# needles_2_5.net
KiCad netlist of a schematic drawn in EAGLE
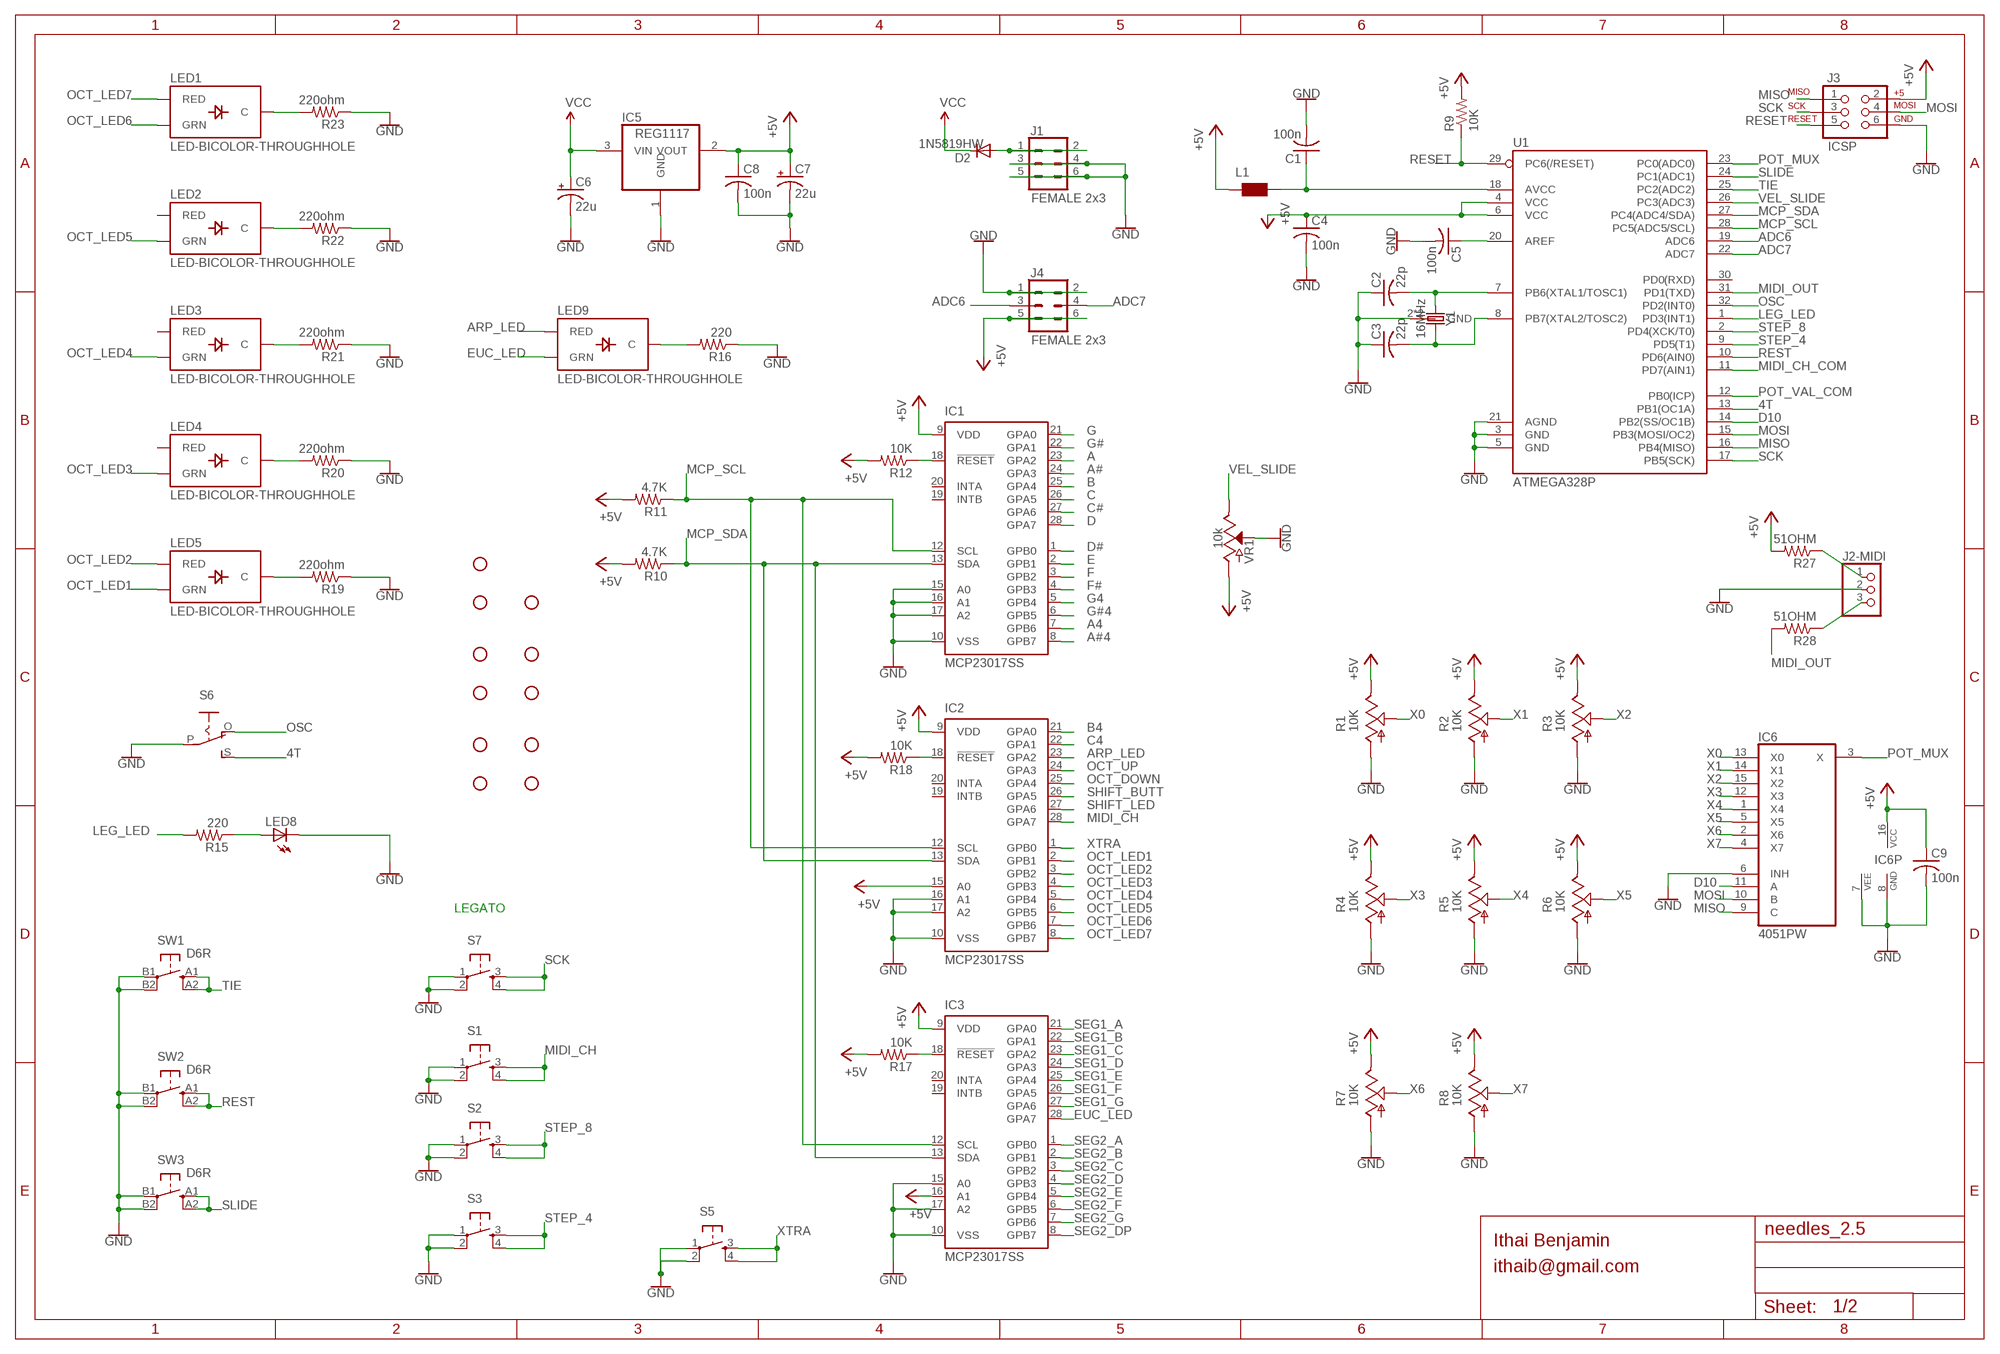
[diagram p0: schematic, sheet 1]
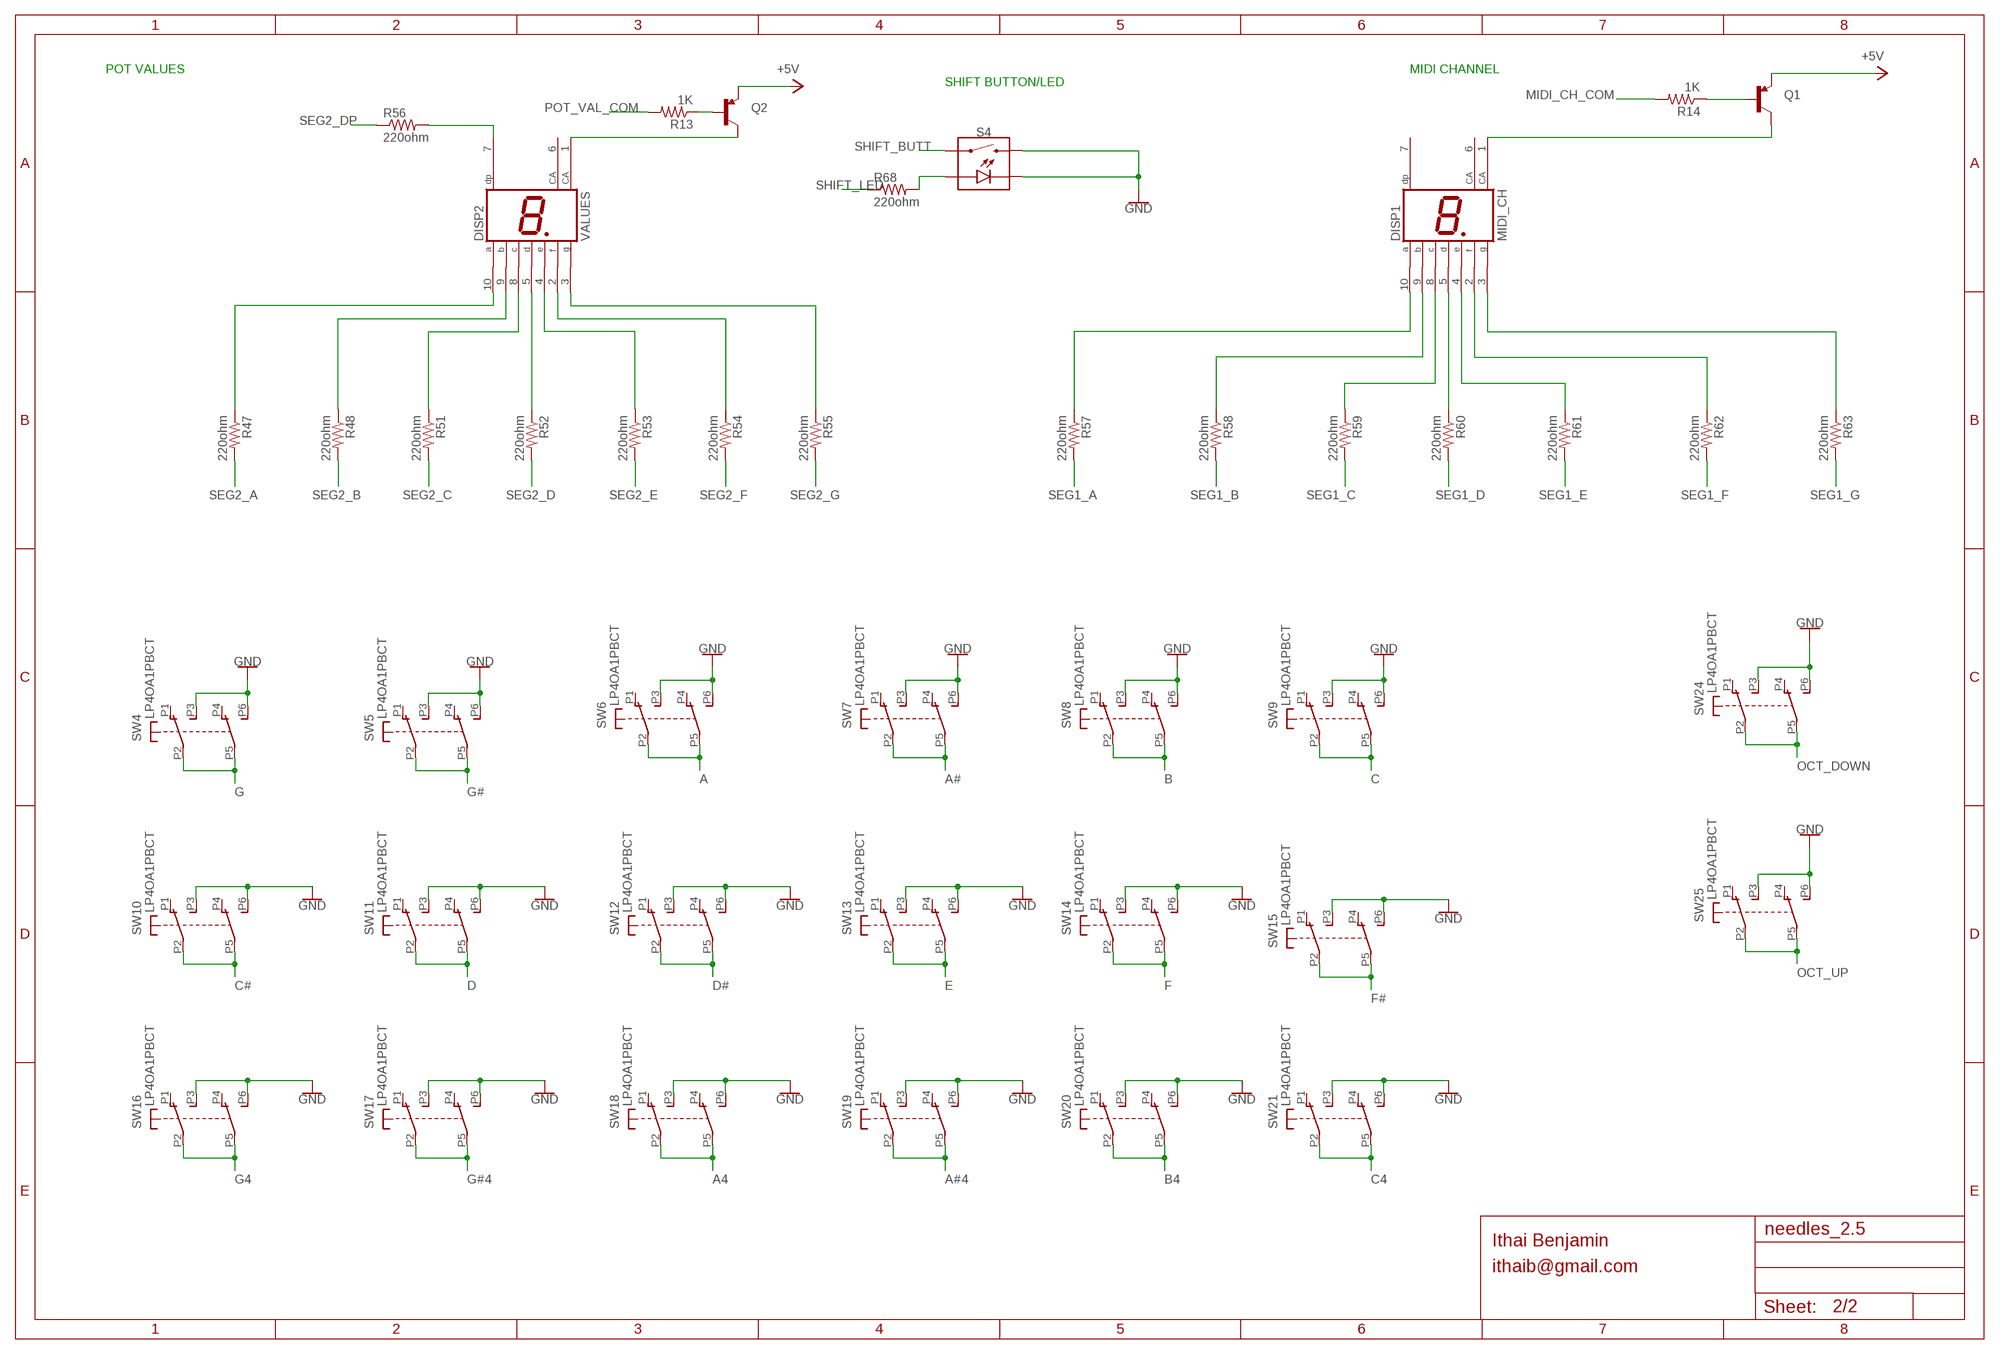
[diagram p1: schematic, sheet 2]

(export (version "E")
  (design (tool "Eeschema 10.0.6"))
  (components
    (comp (ref "DISP1")
      (value "MIDI_CH")
      (footprint "eagle-import:DISPLAY-HP_HDSP-E")
      (libsource (lib "eagle-import") (part "DISPLAY-HP_HD-F101"))
    )
    (comp (ref "DISP2")
      (value "VALUES")
      (footprint "eagle-import:DISPLAY-HP_HDSP-E")
      (libsource (lib "eagle-import") (part "DISPLAY-HP_HD-F101"))
    )
    (comp (ref "Q1")
      (value "TRANSISTOR_PNPSMD")
      (footprint "eagle-import:SOT23-3")
      (libsource (lib "eagle-import") (part "TRANSISTOR_PNPSMD"))
    )
    (comp (ref "Q2")
      (value "TRANSISTOR_PNPSMD")
      (footprint "eagle-import:SOT23-3")
      (libsource (lib "eagle-import") (part "TRANSISTOR_PNPSMD"))
    )
    (comp (ref "R13")
      (value "1K")
      (footprint "eagle-import:R0603")
      (libsource (lib "eagle-import") (part "R-US_R0603"))
    )
    (comp (ref "R14")
      (value "1K")
      (footprint "eagle-import:R0603")
      (libsource (lib "eagle-import") (part "R-US_R0603"))
    )
    (comp (ref "R47")
      (value "220ohm")
      (footprint "eagle-import:R0603")
      (libsource (lib "eagle-import") (part "R-US_R0603"))
    )
    (comp (ref "R48")
      (value "220ohm")
      (footprint "eagle-import:R0603")
      (libsource (lib "eagle-import") (part "R-US_R0603"))
    )
    (comp (ref "R51")
      (value "220ohm")
      (footprint "eagle-import:R0603")
      (libsource (lib "eagle-import") (part "R-US_R0603"))
    )
    (comp (ref "R52")
      (value "220ohm")
      (footprint "eagle-import:R0603")
      (libsource (lib "eagle-import") (part "R-US_R0603"))
    )
    (comp (ref "R53")
      (value "220ohm")
      (footprint "eagle-import:R0603")
      (libsource (lib "eagle-import") (part "R-US_R0603"))
    )
    (comp (ref "R54")
      (value "220ohm")
      (footprint "eagle-import:R0603")
      (libsource (lib "eagle-import") (part "R-US_R0603"))
    )
    (comp (ref "R55")
      (value "220ohm")
      (footprint "eagle-import:R0603")
      (libsource (lib "eagle-import") (part "R-US_R0603"))
    )
    (comp (ref "R56")
      (value "220ohm")
      (footprint "eagle-import:R0603")
      (libsource (lib "eagle-import") (part "R-US_R0603"))
    )
    (comp (ref "R57")
      (value "220ohm")
      (footprint "eagle-import:R0603")
      (libsource (lib "eagle-import") (part "R-US_R0603"))
    )
    (comp (ref "R58")
      (value "220ohm")
      (footprint "eagle-import:R0603")
      (libsource (lib "eagle-import") (part "R-US_R0603"))
    )
    (comp (ref "R59")
      (value "220ohm")
      (footprint "eagle-import:R0603")
      (libsource (lib "eagle-import") (part "R-US_R0603"))
    )
    (comp (ref "R60")
      (value "220ohm")
      (footprint "eagle-import:R0603")
      (libsource (lib "eagle-import") (part "R-US_R0603"))
    )
    (comp (ref "R61")
      (value "220ohm")
      (footprint "eagle-import:R0603")
      (libsource (lib "eagle-import") (part "R-US_R0603"))
    )
    (comp (ref "R62")
      (value "220ohm")
      (footprint "eagle-import:R0603")
      (libsource (lib "eagle-import") (part "R-US_R0603"))
    )
    (comp (ref "R63")
      (value "220ohm")
      (footprint "eagle-import:R0603")
      (libsource (lib "eagle-import") (part "R-US_R0603"))
    )
    (comp (ref "R68")
      (value "220ohm")
      (footprint "eagle-import:R0603")
      (libsource (lib "eagle-import") (part "R-US_R0603"))
    )
    (comp (ref "S4")
      (value "MOMENTARY-SWITCH-SPST-LED-PTH-12MM")
      (footprint "eagle-import:TACTILE_SWITCH_LED_PTH_12MM")
      (libsource (lib "eagle-import") (part "MOMENTARY-SWITCH-SPST-LED-PTH-12MM"))
    )
    (comp (ref "SW4")
      (value "LP4OA1PBCT")
      (footprint "eagle-import:LP4OA1PBCT")
      (libsource (lib "eagle-import") (part "grids_v02_LP4OA1PBCT"))
    )
    (comp (ref "SW5")
      (value "LP4OA1PBCT")
      (footprint "eagle-import:LP4OA1PBCT")
      (libsource (lib "eagle-import") (part "grids_v02_LP4OA1PBCT"))
    )
    (comp (ref "SW6")
      (value "LP4OA1PBCT")
      (footprint "eagle-import:LP4OA1PBCT")
      (libsource (lib "eagle-import") (part "grids_v02_LP4OA1PBCT"))
    )
    (comp (ref "SW7")
      (value "LP4OA1PBCT")
      (footprint "eagle-import:LP4OA1PBCT")
      (libsource (lib "eagle-import") (part "grids_v02_LP4OA1PBCT"))
    )
    (comp (ref "SW8")
      (value "LP4OA1PBCT")
      (footprint "eagle-import:LP4OA1PBCT")
      (libsource (lib "eagle-import") (part "grids_v02_LP4OA1PBCT"))
    )
    (comp (ref "SW9")
      (value "LP4OA1PBCT")
      (footprint "eagle-import:LP4OA1PBCT")
      (libsource (lib "eagle-import") (part "grids_v02_LP4OA1PBCT"))
    )
    (comp (ref "SW10")
      (value "LP4OA1PBCT")
      (footprint "eagle-import:LP4OA1PBCT")
      (libsource (lib "eagle-import") (part "grids_v02_LP4OA1PBCT"))
    )
    (comp (ref "SW11")
      (value "LP4OA1PBCT")
      (footprint "eagle-import:LP4OA1PBCT")
      (libsource (lib "eagle-import") (part "grids_v02_LP4OA1PBCT"))
    )
    (comp (ref "SW12")
      (value "LP4OA1PBCT")
      (footprint "eagle-import:LP4OA1PBCT")
      (libsource (lib "eagle-import") (part "grids_v02_LP4OA1PBCT"))
    )
    (comp (ref "SW13")
      (value "LP4OA1PBCT")
      (footprint "eagle-import:LP4OA1PBCT")
      (libsource (lib "eagle-import") (part "grids_v02_LP4OA1PBCT"))
    )
    (comp (ref "SW14")
      (value "LP4OA1PBCT")
      (footprint "eagle-import:LP4OA1PBCT")
      (libsource (lib "eagle-import") (part "grids_v02_LP4OA1PBCT"))
    )
    (comp (ref "SW15")
      (value "LP4OA1PBCT")
      (footprint "eagle-import:LP4OA1PBCT")
      (libsource (lib "eagle-import") (part "grids_v02_LP4OA1PBCT"))
    )
    (comp (ref "SW16")
      (value "LP4OA1PBCT")
      (footprint "eagle-import:LP4OA1PBCT")
      (libsource (lib "eagle-import") (part "grids_v02_LP4OA1PBCT"))
    )
    (comp (ref "SW17")
      (value "LP4OA1PBCT")
      (footprint "eagle-import:LP4OA1PBCT")
      (libsource (lib "eagle-import") (part "grids_v02_LP4OA1PBCT"))
    )
    (comp (ref "SW18")
      (value "LP4OA1PBCT")
      (footprint "eagle-import:LP4OA1PBCT")
      (libsource (lib "eagle-import") (part "grids_v02_LP4OA1PBCT"))
    )
    (comp (ref "SW19")
      (value "LP4OA1PBCT")
      (footprint "eagle-import:LP4OA1PBCT")
      (libsource (lib "eagle-import") (part "grids_v02_LP4OA1PBCT"))
    )
    (comp (ref "SW20")
      (value "LP4OA1PBCT")
      (footprint "eagle-import:LP4OA1PBCT")
      (libsource (lib "eagle-import") (part "grids_v02_LP4OA1PBCT"))
    )
    (comp (ref "SW21")
      (value "LP4OA1PBCT")
      (footprint "eagle-import:LP4OA1PBCT")
      (libsource (lib "eagle-import") (part "grids_v02_LP4OA1PBCT"))
    )
    (comp (ref "SW24")
      (value "LP4OA1PBCT")
      (footprint "eagle-import:LP4OA1PBCT")
      (libsource (lib "eagle-import") (part "LP4OA1PBCT"))
    )
    (comp (ref "SW25")
      (value "LP4OA1PBCT")
      (footprint "eagle-import:LP4OA1PBCT")
      (libsource (lib "eagle-import") (part "LP4OA1PBCT"))
    )
    (comp (ref "C1")
      (value "100n")
      (footprint "eagle-import:C0603")
      (libsource (lib "eagle-import") (part "C-USC0603"))
    )
    (comp (ref "C2")
      (value "22p")
      (footprint "eagle-import:C0603")
      (libsource (lib "eagle-import") (part "C-USC0603"))
    )
    (comp (ref "C3")
      (value "22p")
      (footprint "eagle-import:C0603")
      (libsource (lib "eagle-import") (part "C-USC0603"))
    )
    (comp (ref "C4")
      (value "100n")
      (footprint "eagle-import:C0603")
      (libsource (lib "eagle-import") (part "C-USC0603"))
    )
    (comp (ref "C5")
      (value "100n")
      (footprint "eagle-import:C0603")
      (libsource (lib "eagle-import") (part "C-USC0603"))
    )
    (comp (ref "C6")
      (value "22u")
      (footprint "eagle-import:PANASONIC_C")
      (libsource (lib "eagle-import") (part "CPOL-USC"))
    )
    (comp (ref "C7")
      (value "22u")
      (footprint "eagle-import:PANASONIC_C")
      (libsource (lib "eagle-import") (part "CPOL-USC"))
    )
    (comp (ref "C8")
      (value "100n")
      (footprint "eagle-import:C0603")
      (libsource (lib "eagle-import") (part "C-USC0603"))
    )
    (comp (ref "C9")
      (value "100n")
      (footprint "eagle-import:C0603")
      (libsource (lib "eagle-import") (part "C-USC0603"))
    )
    (comp (ref "D2")
      (value "1N5819HW")
      (footprint "eagle-import:SOD123")
      (libsource (lib "eagle-import") (part "DIODE-SOD123"))
    )
    (comp (ref "H1")
      (value "STAND-OFF")
      (footprint "eagle-import:STAND-OFF")
      (libsource (lib "eagle-import") (part "STAND-OFF"))
    )
    (comp (ref "H2")
      (value "STAND-OFF")
      (footprint "eagle-import:STAND-OFF")
      (libsource (lib "eagle-import") (part "STAND-OFF"))
    )
    (comp (ref "H3")
      (value "STAND-OFF")
      (footprint "eagle-import:STAND-OFF")
      (libsource (lib "eagle-import") (part "STAND-OFF"))
    )
    (comp (ref "H4")
      (value "STAND-OFF")
      (footprint "eagle-import:STAND-OFF")
      (libsource (lib "eagle-import") (part "STAND-OFF"))
    )
    (comp (ref "H5")
      (value "STAND-OFF")
      (footprint "eagle-import:STAND-OFF")
      (libsource (lib "eagle-import") (part "STAND-OFF"))
    )
    (comp (ref "H6")
      (value "STAND-OFF")
      (footprint "eagle-import:STAND-OFF")
      (libsource (lib "eagle-import") (part "STAND-OFF"))
    )
    (comp (ref "H7")
      (value "STAND-OFF")
      (footprint "eagle-import:STAND-OFF")
      (libsource (lib "eagle-import") (part "STAND-OFF"))
    )
    (comp (ref "H8")
      (value "STAND-OFF")
      (footprint "eagle-import:STAND-OFF")
      (libsource (lib "eagle-import") (part "STAND-OFF"))
    )
    (comp (ref "H9")
      (value "STAND-OFF")
      (footprint "eagle-import:STAND-OFF")
      (libsource (lib "eagle-import") (part "STAND-OFF"))
    )
    (comp (ref "H10")
      (value "STAND-OFF")
      (footprint "eagle-import:STAND-OFF")
      (libsource (lib "eagle-import") (part "STAND-OFF"))
    )
    (comp (ref "H11")
      (value "STAND-OFF")
      (footprint "eagle-import:STAND-OFF")
      (libsource (lib "eagle-import") (part "STAND-OFF"))
    )
    (comp (ref "IC1")
      (value "MCP23017SS")
      (footprint "eagle-import:SSOP28")
      (libsource (lib "eagle-import") (part "MCP23017SS"))
    )
    (comp (ref "IC2")
      (value "MCP23017SS")
      (footprint "eagle-import:SSOP28")
      (libsource (lib "eagle-import") (part "MCP23017SS"))
    )
    (comp (ref "IC3")
      (value "MCP23017SS")
      (footprint "eagle-import:SSOP28")
      (libsource (lib "eagle-import") (part "MCP23017SS"))
    )
    (comp (ref "IC5")
      (value "REG1117")
      (footprint "eagle-import:SOT223")
      (libsource (lib "eagle-import") (part "REG1117"))
    )
    (comp (ref "IC6")
      (value "4051PW")
      (footprint "eagle-import:TSSOP16")
      (libsource (lib "eagle-import") (part "4051PW"))
    )
    (comp (ref "J1")
      (value "FEMALE 2x3")
      (footprint "eagle-import:2X3")
      (libsource (lib "eagle-import") (part "CONN_03X2FEMALE"))
    )
    (comp (ref "J2-MIDI")
      (value "PINHD-1X3")
      (footprint "eagle-import:1X03")
      (libsource (lib "eagle-import") (part "PINHD-1X3"))
    )
    (comp (ref "J3")
      (value "ICSP")
      (footprint "eagle-import:2X3")
      (libsource (lib "eagle-import") (part "AVR_SPI_PRG_6PTH"))
    )
    (comp (ref "J4")
      (value "FEMALE 2x3")
      (footprint "eagle-import:2X3")
      (libsource (lib "eagle-import") (part "CONN_03X2FEMALE"))
    )
    (comp (ref "L1")
      (value "WE-CBF_0603")
      (footprint "eagle-import:0603")
      (libsource (lib "eagle-import") (part "WE-CBF_0603"))
    )
    (comp (ref "LED1")
      (value "LED-BICOLOR-THROUGHHOLE")
      (footprint "eagle-import:LED-BICOLOR-THROUGHHOLE")
      (libsource (lib "eagle-import") (part "LED-BICOLOR-THROUGHHOLE"))
    )
    (comp (ref "LED2")
      (value "LED-BICOLOR-THROUGHHOLE")
      (footprint "eagle-import:LED-BICOLOR-THROUGHHOLE")
      (libsource (lib "eagle-import") (part "LED-BICOLOR-THROUGHHOLE"))
    )
    (comp (ref "LED3")
      (value "LED-BICOLOR-THROUGHHOLE")
      (footprint "eagle-import:LED-BICOLOR-THROUGHHOLE")
      (libsource (lib "eagle-import") (part "LED-BICOLOR-THROUGHHOLE"))
    )
    (comp (ref "LED4")
      (value "LED-BICOLOR-THROUGHHOLE")
      (footprint "eagle-import:LED-BICOLOR-THROUGHHOLE")
      (libsource (lib "eagle-import") (part "LED-BICOLOR-THROUGHHOLE"))
    )
    (comp (ref "LED5")
      (value "LED-BICOLOR-THROUGHHOLE")
      (footprint "eagle-import:LED-BICOLOR-THROUGHHOLE")
      (libsource (lib "eagle-import") (part "LED-BICOLOR-THROUGHHOLE"))
    )
    (comp (ref "LED8")
      (value "LED3MM")
      (footprint "eagle-import:LED3MM")
      (libsource (lib "eagle-import") (part "LED3MM"))
    )
    (comp (ref "LED9")
      (value "LED-BICOLOR-THROUGHHOLE")
      (footprint "eagle-import:LED-BICOLOR-THROUGHHOLE")
      (libsource (lib "eagle-import") (part "LED-BICOLOR-THROUGHHOLE"))
    )
    (comp (ref "R1")
      (value "10K")
      (footprint "eagle-import:ALPS_POT_VERTICAL")
      (libsource (lib "eagle-import") (part "POT_USVERTICAL"))
    )
    (comp (ref "R2")
      (value "10K")
      (footprint "eagle-import:ALPS_POT_VERTICAL")
      (libsource (lib "eagle-import") (part "POT_USVERTICAL"))
    )
    (comp (ref "R3")
      (value "10K")
      (footprint "eagle-import:ALPS_POT_VERTICAL")
      (libsource (lib "eagle-import") (part "POT_USVERTICAL"))
    )
    (comp (ref "R4")
      (value "10K")
      (footprint "eagle-import:ALPS_POT_VERTICAL")
      (libsource (lib "eagle-import") (part "POT_USVERTICAL"))
    )
    (comp (ref "R5")
      (value "10K")
      (footprint "eagle-import:ALPS_POT_VERTICAL")
      (libsource (lib "eagle-import") (part "POT_USVERTICAL"))
    )
    (comp (ref "R6")
      (value "10K")
      (footprint "eagle-import:ALPS_POT_VERTICAL")
      (libsource (lib "eagle-import") (part "POT_USVERTICAL"))
    )
    (comp (ref "R7")
      (value "10K")
      (footprint "eagle-import:ALPS_POT_VERTICAL")
      (libsource (lib "eagle-import") (part "POT_USVERTICAL"))
    )
    (comp (ref "R8")
      (value "10K")
      (footprint "eagle-import:ALPS_POT_VERTICAL")
      (libsource (lib "eagle-import") (part "POT_USVERTICAL"))
    )
    (comp (ref "R9")
      (value "10K")
      (footprint "eagle-import:R0603")
      (libsource (lib "eagle-import") (part "R-US_R0603"))
    )
    (comp (ref "R10")
      (value "4.7K")
      (footprint "eagle-import:R0603")
      (libsource (lib "eagle-import") (part "R-US_R0603"))
    )
    (comp (ref "R11")
      (value "4.7K")
      (footprint "eagle-import:R0603")
      (libsource (lib "eagle-import") (part "R-US_R0603"))
    )
    (comp (ref "R12")
      (value "10K")
      (footprint "eagle-import:R0603")
      (libsource (lib "eagle-import") (part "R-US_R0603"))
    )
    (comp (ref "R15")
      (value "220")
      (footprint "eagle-import:R0603")
      (libsource (lib "eagle-import") (part "R-US_R0603"))
    )
    (comp (ref "R16")
      (value "220")
      (footprint "eagle-import:R0603")
      (libsource (lib "eagle-import") (part "R-US_R0603"))
    )
    (comp (ref "R17")
      (value "10K")
      (footprint "eagle-import:R0603")
      (libsource (lib "eagle-import") (part "R-US_R0603"))
    )
    (comp (ref "R18")
      (value "10K")
      (footprint "eagle-import:R0603")
      (libsource (lib "eagle-import") (part "R-US_R0603"))
    )
    (comp (ref "R19")
      (value "220ohm")
      (footprint "eagle-import:R0603")
      (libsource (lib "eagle-import") (part "R-US_R0603"))
    )
    (comp (ref "R20")
      (value "220ohm")
      (footprint "eagle-import:R0603")
      (libsource (lib "eagle-import") (part "R-US_R0603"))
    )
    (comp (ref "R21")
      (value "220ohm")
      (footprint "eagle-import:R0603")
      (libsource (lib "eagle-import") (part "R-US_R0603"))
    )
    (comp (ref "R22")
      (value "220ohm")
      (footprint "eagle-import:R0603")
      (libsource (lib "eagle-import") (part "R-US_R0603"))
    )
    (comp (ref "R23")
      (value "220ohm")
      (footprint "eagle-import:R0603")
      (libsource (lib "eagle-import") (part "R-US_R0603"))
    )
    (comp (ref "R27")
      (value "51OHM")
      (footprint "eagle-import:R0603")
      (libsource (lib "eagle-import") (part "R-US_R0603"))
    )
    (comp (ref "R28")
      (value "51OHM")
      (footprint "eagle-import:R0603")
      (libsource (lib "eagle-import") (part "R-US_R0603"))
    )
    (comp (ref "S1")
      (value "TAC_SWITCHPTH")
      (footprint "eagle-import:TACTILE-PTH")
      (libsource (lib "eagle-import") (part "TAC_SWITCHPTH"))
    )
    (comp (ref "S2")
      (value "TAC_SWITCHPTH")
      (footprint "eagle-import:TACTILE-PTH")
      (libsource (lib "eagle-import") (part "TAC_SWITCHPTH"))
    )
    (comp (ref "S3")
      (value "TAC_SWITCHPTH")
      (footprint "eagle-import:TACTILE-PTH")
      (libsource (lib "eagle-import") (part "TAC_SWITCHPTH"))
    )
    (comp (ref "S5")
      (value "TAC_SWITCHPTH")
      (footprint "eagle-import:TACTILE-PTH")
      (libsource (lib "eagle-import") (part "TAC_SWITCHPTH"))
    )
    (comp (ref "S6")
      (value "S-ON-ONSMALL_SLIDE")
      (footprint "eagle-import:ES_100SP1T6B11M2QEH_SMALL")
      (libsource (lib "eagle-import") (part "S-ON-ONSMALL_SLIDE"))
    )
    (comp (ref "S7")
      (value "TAC_SWITCHPTH")
      (footprint "eagle-import:TACTILE-PTH")
      (libsource (lib "eagle-import") (part "TAC_SWITCHPTH"))
    )
    (comp (ref "SW1")
      (value "D6R")
      (footprint "eagle-import:D6R")
      (libsource (lib "eagle-import") (part "D6R"))
    )
    (comp (ref "SW2")
      (value "D6R")
      (footprint "eagle-import:D6R")
      (libsource (lib "eagle-import") (part "D6R"))
    )
    (comp (ref "SW3")
      (value "D6R")
      (footprint "eagle-import:D6R")
      (libsource (lib "eagle-import") (part "D6R"))
    )
    (comp (ref "U1")
      (value "ATMEGA328P")
      (footprint "eagle-import:TQFP32-08")
      (libsource (lib "eagle-import") (part "ATMEGA328P_TQFP"))
    )
    (comp (ref "VR1")
      (value "10k")
      (footprint "eagle-import:SLIDER-MEDIUM")
      (libsource (lib "eagle-import") (part "POTENTIOMETER_SLIDE-30MM-1/10W-20%"))
    )
    (comp (ref "Y1")
      (value "16MHz")
      (footprint "eagle-import:CRYSTAL-SMD-5X3.2-4PAD")
      (libsource (lib "eagle-import") (part "CRYSTAL-16MHZSMD-5X3.2"))
    )
  )
  (nets
    (net (code "1") (name "+5V") (class "Default")
      (node (ref "C4") (pin "1") (pinfunction "1_1") (pintype "passive"))
      (node (ref "C7") (pin "+") (pinfunction "+_+") (pintype "passive"))
      (node (ref "C8") (pin "1") (pinfunction "1_1") (pintype "passive"))
      (node (ref "C9") (pin "1") (pinfunction "1_1") (pintype "passive"))
      (node (ref "IC1") (pin "9") (pinfunction "VDD_9") (pintype "power_in"))
      (node (ref "IC2") (pin "15") (pinfunction "A0_15") (pintype "input"))
      (node (ref "IC2") (pin "9") (pinfunction "VDD_9") (pintype "power_in"))
      (node (ref "IC3") (pin "16") (pinfunction "A1_16") (pintype "input"))
      (node (ref "IC3") (pin "9") (pinfunction "VDD_9") (pintype "power_in"))
      (node (ref "IC5") (pin "2") (pinfunction "VOUT_2") (pintype "power_in"))
      (node (ref "IC6") (pin "16") (pinfunction "VCC_16") (pintype "power_in"))
      (node (ref "J3") (pin "2") (pinfunction "2_2") (pintype "passive"))
      (node (ref "J4") (pin "5") (pinfunction "5_5") (pintype "bidirectional"))
      (node (ref "J4") (pin "6") (pinfunction "6_6") (pintype "bidirectional"))
      (node (ref "L1") (pin "1") (pinfunction "1_1") (pintype "passive"))
      (node (ref "Q1") (pin "2") (pinfunction "E_2") (pintype "passive"))
      (node (ref "Q2") (pin "2") (pinfunction "E_2") (pintype "passive"))
      (node (ref "R1") (pin "P$1") (pinfunction "E_P$1") (pintype "passive"))
      (node (ref "R10") (pin "2") (pinfunction "2_2") (pintype "passive"))
      (node (ref "R11") (pin "2") (pinfunction "2_2") (pintype "passive"))
      (node (ref "R12") (pin "2") (pinfunction "2_2") (pintype "passive"))
      (node (ref "R17") (pin "2") (pinfunction "2_2") (pintype "passive"))
      (node (ref "R18") (pin "2") (pinfunction "2_2") (pintype "passive"))
      (node (ref "R2") (pin "P$1") (pinfunction "E_P$1") (pintype "passive"))
      (node (ref "R27") (pin "2") (pinfunction "2_2") (pintype "passive"))
      (node (ref "R3") (pin "P$1") (pinfunction "E_P$1") (pintype "passive"))
      (node (ref "R4") (pin "P$1") (pinfunction "E_P$1") (pintype "passive"))
      (node (ref "R5") (pin "P$1") (pinfunction "E_P$1") (pintype "passive"))
      (node (ref "R6") (pin "P$1") (pinfunction "E_P$1") (pintype "passive"))
      (node (ref "R7") (pin "P$1") (pinfunction "E_P$1") (pintype "passive"))
      (node (ref "R8") (pin "P$1") (pinfunction "E_P$1") (pintype "passive"))
      (node (ref "R9") (pin "2") (pinfunction "2_2") (pintype "passive"))
      (node (ref "U1") (pin "4") (pinfunction "VCC_4") (pintype "bidirectional"))
      (node (ref "U1") (pin "6") (pinfunction "VCC_6") (pintype "bidirectional"))
      (node (ref "VR1") (pin "BOTTOM") (pinfunction "A_BOTTOM") (pintype "passive"))
    )
    (net (code "2") (name "4T") (class "Default")
      (node (ref "S6") (pin "S") (pinfunction "S_S") (pintype "passive"))
      (node (ref "U1") (pin "13") (pinfunction "PB1(OC1A)_13") (pintype "bidirectional"))
    )
    (net (code "3") (name "A") (class "Default")
      (node (ref "IC1") (pin "23") (pinfunction "GPA2_23") (pintype "bidirectional"))
      (node (ref "SW6") (pin "P2") (pinfunction "A2_P2") (pintype "passive"))
      (node (ref "SW6") (pin "P5") (pinfunction "B2_P5") (pintype "passive"))
    )
    (net (code "4") (name "A#") (class "Default")
      (node (ref "IC1") (pin "24") (pinfunction "GPA3_24") (pintype "bidirectional"))
      (node (ref "SW7") (pin "P2") (pinfunction "A2_P2") (pintype "passive"))
      (node (ref "SW7") (pin "P5") (pinfunction "B2_P5") (pintype "passive"))
    )
    (net (code "5") (name "A#4") (class "Default")
      (node (ref "IC1") (pin "8") (pinfunction "GPB7_8") (pintype "bidirectional"))
      (node (ref "SW19") (pin "P2") (pinfunction "A2_P2") (pintype "passive"))
      (node (ref "SW19") (pin "P5") (pinfunction "B2_P5") (pintype "passive"))
    )
    (net (code "6") (name "A4") (class "Default")
      (node (ref "IC1") (pin "7") (pinfunction "GPB6_7") (pintype "bidirectional"))
      (node (ref "SW18") (pin "P2") (pinfunction "A2_P2") (pintype "passive"))
      (node (ref "SW18") (pin "P5") (pinfunction "B2_P5") (pintype "passive"))
    )
    (net (code "7") (name "ADC6") (class "Default")
      (node (ref "J4") (pin "3") (pinfunction "3_3") (pintype "bidirectional"))
      (node (ref "U1") (pin "19") (pinfunction "ADC6_19") (pintype "bidirectional"))
    )
    (net (code "8") (name "ADC7") (class "Default")
      (node (ref "J4") (pin "4") (pinfunction "4_4") (pintype "bidirectional"))
      (node (ref "U1") (pin "22") (pinfunction "ADC7_22") (pintype "bidirectional"))
    )
    (net (code "9") (name "ARP_LED") (class "Default")
      (node (ref "IC2") (pin "23") (pinfunction "GPA2_23") (pintype "bidirectional"))
      (node (ref "LED9") (pin "3") (pinfunction "RED_3") (pintype "bidirectional"))
    )
    (net (code "10") (name "B") (class "Default")
      (node (ref "IC1") (pin "25") (pinfunction "GPA4_25") (pintype "bidirectional"))
      (node (ref "SW8") (pin "P2") (pinfunction "A2_P2") (pintype "passive"))
      (node (ref "SW8") (pin "P5") (pinfunction "B2_P5") (pintype "passive"))
    )
    (net (code "11") (name "B4") (class "Default")
      (node (ref "IC2") (pin "21") (pinfunction "GPA0_21") (pintype "bidirectional"))
      (node (ref "SW20") (pin "P2") (pinfunction "A2_P2") (pintype "passive"))
      (node (ref "SW20") (pin "P5") (pinfunction "B2_P5") (pintype "passive"))
    )
    (net (code "12") (name "C") (class "Default")
      (node (ref "IC1") (pin "26") (pinfunction "GPA5_26") (pintype "bidirectional"))
      (node (ref "SW9") (pin "P2") (pinfunction "A2_P2") (pintype "passive"))
      (node (ref "SW9") (pin "P5") (pinfunction "B2_P5") (pintype "passive"))
    )
    (net (code "13") (name "C#") (class "Default")
      (node (ref "IC1") (pin "27") (pinfunction "GPA6_27") (pintype "bidirectional"))
      (node (ref "SW10") (pin "P2") (pinfunction "A2_P2") (pintype "passive"))
      (node (ref "SW10") (pin "P5") (pinfunction "B2_P5") (pintype "passive"))
    )
    (net (code "14") (name "C4") (class "Default")
      (node (ref "IC2") (pin "22") (pinfunction "GPA1_22") (pintype "bidirectional"))
      (node (ref "SW21") (pin "P2") (pinfunction "A2_P2") (pintype "passive"))
      (node (ref "SW21") (pin "P5") (pinfunction "B2_P5") (pintype "passive"))
    )
    (net (code "15") (name "D") (class "Default")
      (node (ref "IC1") (pin "28") (pinfunction "GPA7_28") (pintype "bidirectional"))
      (node (ref "SW11") (pin "P2") (pinfunction "A2_P2") (pintype "passive"))
      (node (ref "SW11") (pin "P5") (pinfunction "B2_P5") (pintype "passive"))
    )
    (net (code "16") (name "D#") (class "Default")
      (node (ref "IC1") (pin "1") (pinfunction "GPB0_1") (pintype "bidirectional"))
      (node (ref "SW12") (pin "P2") (pinfunction "A2_P2") (pintype "passive"))
      (node (ref "SW12") (pin "P5") (pinfunction "B2_P5") (pintype "passive"))
    )
    (net (code "17") (name "D10") (class "Default")
      (node (ref "IC6") (pin "11") (pinfunction "A_11") (pintype "input"))
      (node (ref "U1") (pin "14") (pinfunction "PB2(SS/OC1B)_14") (pintype "bidirectional"))
    )
    (net (code "18") (name "E") (class "Default")
      (node (ref "IC1") (pin "2") (pinfunction "GPB1_2") (pintype "bidirectional"))
      (node (ref "SW13") (pin "P2") (pinfunction "A2_P2") (pintype "passive"))
      (node (ref "SW13") (pin "P5") (pinfunction "B2_P5") (pintype "passive"))
    )
    (net (code "19") (name "EUC_LED") (class "Default")
      (node (ref "IC3") (pin "28") (pinfunction "GPA7_28") (pintype "bidirectional"))
      (node (ref "LED9") (pin "1") (pinfunction "GRN_1") (pintype "bidirectional"))
    )
    (net (code "20") (name "F") (class "Default")
      (node (ref "IC1") (pin "3") (pinfunction "GPB2_3") (pintype "bidirectional"))
      (node (ref "SW14") (pin "P2") (pinfunction "A2_P2") (pintype "passive"))
      (node (ref "SW14") (pin "P5") (pinfunction "B2_P5") (pintype "passive"))
    )
    (net (code "21") (name "F#") (class "Default")
      (node (ref "IC1") (pin "4") (pinfunction "GPB3_4") (pintype "bidirectional"))
      (node (ref "SW15") (pin "P2") (pinfunction "A2_P2") (pintype "passive"))
      (node (ref "SW15") (pin "P5") (pinfunction "B2_P5") (pintype "passive"))
    )
    (net (code "22") (name "G") (class "Default")
      (node (ref "IC1") (pin "21") (pinfunction "GPA0_21") (pintype "bidirectional"))
      (node (ref "SW4") (pin "P2") (pinfunction "A2_P2") (pintype "passive"))
      (node (ref "SW4") (pin "P5") (pinfunction "B2_P5") (pintype "passive"))
    )
    (net (code "23") (name "G#") (class "Default")
      (node (ref "IC1") (pin "22") (pinfunction "GPA1_22") (pintype "bidirectional"))
      (node (ref "SW5") (pin "P2") (pinfunction "A2_P2") (pintype "passive"))
      (node (ref "SW5") (pin "P5") (pinfunction "B2_P5") (pintype "passive"))
    )
    (net (code "24") (name "G#4") (class "Default")
      (node (ref "IC1") (pin "6") (pinfunction "GPB5_6") (pintype "bidirectional"))
      (node (ref "SW17") (pin "P2") (pinfunction "A2_P2") (pintype "passive"))
      (node (ref "SW17") (pin "P5") (pinfunction "B2_P5") (pintype "passive"))
    )
    (net (code "25") (name "G4") (class "Default")
      (node (ref "IC1") (pin "5") (pinfunction "GPB4_5") (pintype "bidirectional"))
      (node (ref "SW16") (pin "P2") (pinfunction "A2_P2") (pintype "passive"))
      (node (ref "SW16") (pin "P5") (pinfunction "B2_P5") (pintype "passive"))
    )
    (net (code "26") (name "GND") (class "Default")
      (node (ref "C1") (pin "2") (pinfunction "2_2") (pintype "passive"))
      (node (ref "C2") (pin "1") (pinfunction "1_1") (pintype "passive"))
      (node (ref "C3") (pin "1") (pinfunction "1_1") (pintype "passive"))
      (node (ref "C4") (pin "2") (pinfunction "2_2") (pintype "passive"))
      (node (ref "C5") (pin "2") (pinfunction "2_2") (pintype "passive"))
      (node (ref "C6") (pin "-") (pinfunction "-_-") (pintype "passive"))
      (node (ref "C7") (pin "-") (pinfunction "-_-") (pintype "passive"))
      (node (ref "C8") (pin "2") (pinfunction "2_2") (pintype "passive"))
      (node (ref "C9") (pin "2") (pinfunction "2_2") (pintype "passive"))
      (node (ref "IC1") (pin "10") (pinfunction "VSS_10") (pintype "power_in"))
      (node (ref "IC1") (pin "15") (pinfunction "A0_15") (pintype "input"))
      (node (ref "IC1") (pin "16") (pinfunction "A1_16") (pintype "input"))
      (node (ref "IC1") (pin "17") (pinfunction "A2_17") (pintype "input"))
      (node (ref "IC2") (pin "10") (pinfunction "VSS_10") (pintype "power_in"))
      (node (ref "IC2") (pin "16") (pinfunction "A1_16") (pintype "input"))
      (node (ref "IC2") (pin "17") (pinfunction "A2_17") (pintype "input"))
      (node (ref "IC3") (pin "10") (pinfunction "VSS_10") (pintype "power_in"))
      (node (ref "IC3") (pin "15") (pinfunction "A0_15") (pintype "input"))
      (node (ref "IC3") (pin "17") (pinfunction "A2_17") (pintype "input"))
      (node (ref "IC5") (pin "1") (pinfunction "GND_1") (pintype "power_in"))
      (node (ref "IC6") (pin "6") (pinfunction "INH_6") (pintype "input"))
      (node (ref "IC6") (pin "7") (pinfunction "VEE_7") (pintype "power_in"))
      (node (ref "IC6") (pin "8") (pinfunction "GND_8") (pintype "power_in"))
      (node (ref "J1") (pin "3") (pinfunction "3_3") (pintype "bidirectional"))
      (node (ref "J1") (pin "4") (pinfunction "4_4") (pintype "bidirectional"))
      (node (ref "J1") (pin "5") (pinfunction "5_5") (pintype "bidirectional"))
      (node (ref "J1") (pin "6") (pinfunction "6_6") (pintype "bidirectional"))
      (node (ref "J2-MIDI") (pin "2") (pinfunction "2_2") (pintype "passive"))
      (node (ref "J3") (pin "6") (pinfunction "6_6") (pintype "passive"))
      (node (ref "J4") (pin "1") (pinfunction "1_1") (pintype "bidirectional"))
      (node (ref "J4") (pin "2") (pinfunction "2_2") (pintype "bidirectional"))
      (node (ref "LED8") (pin "K") (pinfunction "C_K") (pintype "passive"))
      (node (ref "R1") (pin "P$3") (pinfunction "A_P$3") (pintype "passive"))
      (node (ref "R16") (pin "1") (pinfunction "1_1") (pintype "passive"))
      (node (ref "R19") (pin "1") (pinfunction "1_1") (pintype "passive"))
      (node (ref "R2") (pin "P$3") (pinfunction "A_P$3") (pintype "passive"))
      (node (ref "R20") (pin "1") (pinfunction "1_1") (pintype "passive"))
      (node (ref "R21") (pin "1") (pinfunction "1_1") (pintype "passive"))
      (node (ref "R22") (pin "1") (pinfunction "1_1") (pintype "passive"))
      (node (ref "R23") (pin "1") (pinfunction "1_1") (pintype "passive"))
      (node (ref "R3") (pin "P$3") (pinfunction "A_P$3") (pintype "passive"))
      (node (ref "R4") (pin "P$3") (pinfunction "A_P$3") (pintype "passive"))
      (node (ref "R5") (pin "P$3") (pinfunction "A_P$3") (pintype "passive"))
      (node (ref "R6") (pin "P$3") (pinfunction "A_P$3") (pintype "passive"))
      (node (ref "R7") (pin "P$3") (pinfunction "A_P$3") (pintype "passive"))
      (node (ref "R8") (pin "P$3") (pinfunction "A_P$3") (pintype "passive"))
      (node (ref "S1") (pin "1") (pinfunction "1_1") (pintype "passive"))
      (node (ref "S1") (pin "2") (pinfunction "2_2") (pintype "passive"))
      (node (ref "S2") (pin "1") (pinfunction "1_1") (pintype "passive"))
      (node (ref "S2") (pin "2") (pinfunction "2_2") (pintype "passive"))
      (node (ref "S3") (pin "1") (pinfunction "1_1") (pintype "passive"))
      (node (ref "S3") (pin "2") (pinfunction "2_2") (pintype "passive"))
      (node (ref "S4") (pin "1") (pinfunction "2_1") (pintype "passive"))
      (node (ref "S4") (pin "2") (pinfunction "2_2") (pintype "passive"))
      (node (ref "S4") (pin "C") (pinfunction "C_C") (pintype "passive"))
      (node (ref "S5") (pin "1") (pinfunction "1_1") (pintype "passive"))
      (node (ref "S5") (pin "2") (pinfunction "2_2") (pintype "passive"))
      (node (ref "S6") (pin "P") (pinfunction "P_P") (pintype "passive"))
      (node (ref "S7") (pin "1") (pinfunction "1_1") (pintype "passive"))
      (node (ref "S7") (pin "2") (pinfunction "2_2") (pintype "passive"))
      (node (ref "SW1") (pin "B1") (pinfunction "P_B1") (pintype "passive"))
      (node (ref "SW1") (pin "B2") (pinfunction "P1_B2") (pintype "passive"))
      (node (ref "SW10") (pin "P3") (pinfunction "A3_P3") (pintype "passive"))
      (node (ref "SW10") (pin "P6") (pinfunction "B3_P6") (pintype "passive"))
      (node (ref "SW11") (pin "P3") (pinfunction "A3_P3") (pintype "passive"))
      (node (ref "SW11") (pin "P6") (pinfunction "B3_P6") (pintype "passive"))
      (node (ref "SW12") (pin "P3") (pinfunction "A3_P3") (pintype "passive"))
      (node (ref "SW12") (pin "P6") (pinfunction "B3_P6") (pintype "passive"))
      (node (ref "SW13") (pin "P3") (pinfunction "A3_P3") (pintype "passive"))
      (node (ref "SW13") (pin "P6") (pinfunction "B3_P6") (pintype "passive"))
      (node (ref "SW14") (pin "P3") (pinfunction "A3_P3") (pintype "passive"))
      (node (ref "SW14") (pin "P6") (pinfunction "B3_P6") (pintype "passive"))
      (node (ref "SW15") (pin "P3") (pinfunction "A3_P3") (pintype "passive"))
      (node (ref "SW15") (pin "P6") (pinfunction "B3_P6") (pintype "passive"))
      (node (ref "SW16") (pin "P3") (pinfunction "A3_P3") (pintype "passive"))
      (node (ref "SW16") (pin "P6") (pinfunction "B3_P6") (pintype "passive"))
      (node (ref "SW17") (pin "P3") (pinfunction "A3_P3") (pintype "passive"))
      (node (ref "SW17") (pin "P6") (pinfunction "B3_P6") (pintype "passive"))
      (node (ref "SW18") (pin "P3") (pinfunction "A3_P3") (pintype "passive"))
      (node (ref "SW18") (pin "P6") (pinfunction "B3_P6") (pintype "passive"))
      (node (ref "SW19") (pin "P3") (pinfunction "A3_P3") (pintype "passive"))
      (node (ref "SW19") (pin "P6") (pinfunction "B3_P6") (pintype "passive"))
      (node (ref "SW2") (pin "B1") (pinfunction "P_B1") (pintype "passive"))
      (node (ref "SW2") (pin "B2") (pinfunction "P1_B2") (pintype "passive"))
      (node (ref "SW20") (pin "P3") (pinfunction "A3_P3") (pintype "passive"))
      (node (ref "SW20") (pin "P6") (pinfunction "B3_P6") (pintype "passive"))
      (node (ref "SW21") (pin "P3") (pinfunction "A3_P3") (pintype "passive"))
      (node (ref "SW21") (pin "P6") (pinfunction "B3_P6") (pintype "passive"))
      (node (ref "SW24") (pin "P3") (pinfunction "A3_P3") (pintype "passive"))
      (node (ref "SW24") (pin "P6") (pinfunction "B3_P6") (pintype "passive"))
      (node (ref "SW25") (pin "P3") (pinfunction "A3_P3") (pintype "passive"))
      (node (ref "SW25") (pin "P6") (pinfunction "B3_P6") (pintype "passive"))
      (node (ref "SW3") (pin "B1") (pinfunction "P_B1") (pintype "passive"))
      (node (ref "SW3") (pin "B2") (pinfunction "P1_B2") (pintype "passive"))
      (node (ref "SW4") (pin "P3") (pinfunction "A3_P3") (pintype "passive"))
      (node (ref "SW4") (pin "P6") (pinfunction "B3_P6") (pintype "passive"))
      (node (ref "SW5") (pin "P3") (pinfunction "A3_P3") (pintype "passive"))
      (node (ref "SW5") (pin "P6") (pinfunction "B3_P6") (pintype "passive"))
      (node (ref "SW6") (pin "P3") (pinfunction "A3_P3") (pintype "passive"))
      (node (ref "SW6") (pin "P6") (pinfunction "B3_P6") (pintype "passive"))
      (node (ref "SW7") (pin "P3") (pinfunction "A3_P3") (pintype "passive"))
      (node (ref "SW7") (pin "P6") (pinfunction "B3_P6") (pintype "passive"))
      (node (ref "SW8") (pin "P3") (pinfunction "A3_P3") (pintype "passive"))
      (node (ref "SW8") (pin "P6") (pinfunction "B3_P6") (pintype "passive"))
      (node (ref "SW9") (pin "P3") (pinfunction "A3_P3") (pintype "passive"))
      (node (ref "SW9") (pin "P6") (pinfunction "B3_P6") (pintype "passive"))
      (node (ref "U1") (pin "21") (pinfunction "AGND_21") (pintype "bidirectional"))
      (node (ref "U1") (pin "3") (pinfunction "GND_3") (pintype "bidirectional"))
      (node (ref "U1") (pin "5") (pinfunction "GND_5") (pintype "bidirectional"))
      (node (ref "VR1") (pin "WIPER") (pinfunction "S_WIPER") (pintype "passive"))
      (node (ref "Y1") (pin "2") (pinfunction "GND_2") (pintype "power_in"))
      (node (ref "Y1") (pin "4") (pinfunction "GND_4") (pintype "power_in"))
    )
    (net (code "27") (name "LEG_LED") (class "Default")
      (node (ref "R15") (pin "2") (pinfunction "2_2") (pintype "passive"))
      (node (ref "U1") (pin "1") (pinfunction "PD3(INT1)_1") (pintype "bidirectional"))
    )
    (net (code "28") (name "MCP_SCL") (class "Default")
      (node (ref "IC1") (pin "12") (pinfunction "SCL_12") (pintype "input"))
      (node (ref "IC2") (pin "12") (pinfunction "SCL_12") (pintype "input"))
      (node (ref "IC3") (pin "12") (pinfunction "SCL_12") (pintype "input"))
      (node (ref "R11") (pin "1") (pinfunction "1_1") (pintype "passive"))
      (node (ref "U1") (pin "28") (pinfunction "PC5(ADC5/SCL)_28") (pintype "bidirectional"))
    )
    (net (code "29") (name "MCP_SDA") (class "Default")
      (node (ref "IC1") (pin "13") (pinfunction "SDA_13") (pintype "bidirectional"))
      (node (ref "IC2") (pin "13") (pinfunction "SDA_13") (pintype "bidirectional"))
      (node (ref "IC3") (pin "13") (pinfunction "SDA_13") (pintype "bidirectional"))
      (node (ref "R10") (pin "1") (pinfunction "1_1") (pintype "passive"))
      (node (ref "U1") (pin "27") (pinfunction "PC4(ADC4/SDA)_27") (pintype "bidirectional"))
    )
    (net (code "30") (name "MIDI_CH") (class "Default")
      (node (ref "IC2") (pin "28") (pinfunction "GPA7_28") (pintype "bidirectional"))
      (node (ref "S1") (pin "3") (pinfunction "3_3") (pintype "passive"))
      (node (ref "S1") (pin "4") (pinfunction "4_4") (pintype "passive"))
    )
    (net (code "31") (name "MIDI_CH_COM") (class "Default")
      (node (ref "R14") (pin "2") (pinfunction "2_2") (pintype "passive"))
      (node (ref "U1") (pin "11") (pinfunction "PD7(AIN1)_11") (pintype "bidirectional"))
    )
    (net (code "32") (name "MIDI_OUT") (class "Default")
      (node (ref "R28") (pin "2") (pinfunction "2_2") (pintype "passive"))
      (node (ref "U1") (pin "31") (pinfunction "PD1(TXD)_31") (pintype "bidirectional"))
    )
    (net (code "33") (name "MISO") (class "Default")
      (node (ref "IC6") (pin "9") (pinfunction "C_9") (pintype "input"))
      (node (ref "J3") (pin "1") (pinfunction "1_1") (pintype "passive"))
      (node (ref "U1") (pin "16") (pinfunction "PB4(MISO)_16") (pintype "bidirectional"))
    )
    (net (code "34") (name "MOSI") (class "Default")
      (node (ref "IC6") (pin "10") (pinfunction "B_10") (pintype "input"))
      (node (ref "J3") (pin "4") (pinfunction "4_4") (pintype "passive"))
      (node (ref "U1") (pin "15") (pinfunction "PB3(MOSI/OC2)_15") (pintype "bidirectional"))
    )
    (net (code "35") (name "Net-(D2-PadA)") (class "Default")
      (node (ref "D2") (pin "A") (pinfunction "A_A") (pintype "passive"))
      (node (ref "J1") (pin "1") (pinfunction "1_1") (pintype "bidirectional"))
      (node (ref "J1") (pin "2") (pinfunction "2_2") (pintype "bidirectional"))
    )
    (net (code "36") (name "Net-(DISP1-A)") (class "Default")
      (node (ref "DISP1") (pin "10") (pinfunction "A_10") (pintype "passive"))
      (node (ref "R57") (pin "1") (pinfunction "1_1") (pintype "passive"))
    )
    (net (code "37") (name "Net-(DISP1-B)") (class "Default")
      (node (ref "DISP1") (pin "9") (pinfunction "B_9") (pintype "passive"))
      (node (ref "R58") (pin "1") (pinfunction "1_1") (pintype "passive"))
    )
    (net (code "38") (name "Net-(DISP1-C)") (class "Default")
      (node (ref "DISP1") (pin "8") (pinfunction "C_8") (pintype "passive"))
      (node (ref "R59") (pin "1") (pinfunction "1_1") (pintype "passive"))
    )
    (net (code "39") (name "Net-(DISP1-D)") (class "Default")
      (node (ref "DISP1") (pin "5") (pinfunction "D_5") (pintype "passive"))
      (node (ref "R60") (pin "1") (pinfunction "1_1") (pintype "passive"))
    )
    (net (code "40") (name "Net-(DISP1-E)") (class "Default")
      (node (ref "DISP1") (pin "4") (pinfunction "E_4") (pintype "passive"))
      (node (ref "R61") (pin "1") (pinfunction "1_1") (pintype "passive"))
    )
    (net (code "41") (name "Net-(DISP1-F)") (class "Default")
      (node (ref "DISP1") (pin "2") (pinfunction "F_2") (pintype "passive"))
      (node (ref "R62") (pin "1") (pinfunction "1_1") (pintype "passive"))
    )
    (net (code "42") (name "Net-(DISP1-G)") (class "Default")
      (node (ref "DISP1") (pin "3") (pinfunction "G_3") (pintype "passive"))
      (node (ref "R63") (pin "1") (pinfunction "1_1") (pintype "passive"))
    )
    (net (code "43") (name "Net-(DISP2-A)") (class "Default")
      (node (ref "DISP2") (pin "10") (pinfunction "A_10") (pintype "passive"))
      (node (ref "R47") (pin "1") (pinfunction "1_1") (pintype "passive"))
    )
    (net (code "44") (name "Net-(DISP2-B)") (class "Default")
      (node (ref "DISP2") (pin "9") (pinfunction "B_9") (pintype "passive"))
      (node (ref "R48") (pin "1") (pinfunction "1_1") (pintype "passive"))
    )
    (net (code "45") (name "Net-(DISP2-C)") (class "Default")
      (node (ref "DISP2") (pin "8") (pinfunction "C_8") (pintype "passive"))
      (node (ref "R51") (pin "1") (pinfunction "1_1") (pintype "passive"))
    )
    (net (code "46") (name "Net-(DISP2-D)") (class "Default")
      (node (ref "DISP2") (pin "5") (pinfunction "D_5") (pintype "passive"))
      (node (ref "R52") (pin "1") (pinfunction "1_1") (pintype "passive"))
    )
    (net (code "47") (name "Net-(DISP2-DP)") (class "Default")
      (node (ref "DISP2") (pin "7") (pinfunction "DP_7") (pintype "passive"))
      (node (ref "R56") (pin "2") (pinfunction "2_2") (pintype "passive"))
    )
    (net (code "48") (name "Net-(DISP2-E)") (class "Default")
      (node (ref "DISP2") (pin "4") (pinfunction "E_4") (pintype "passive"))
      (node (ref "R53") (pin "1") (pinfunction "1_1") (pintype "passive"))
    )
    (net (code "49") (name "Net-(DISP2-F)") (class "Default")
      (node (ref "DISP2") (pin "2") (pinfunction "F_2") (pintype "passive"))
      (node (ref "R54") (pin "1") (pinfunction "1_1") (pintype "passive"))
    )
    (net (code "50") (name "Net-(DISP2-G)") (class "Default")
      (node (ref "DISP2") (pin "3") (pinfunction "G_3") (pintype "passive"))
      (node (ref "R55") (pin "1") (pinfunction "1_1") (pintype "passive"))
    )
    (net (code "51") (name "Net-(IC1-~{RESET})") (class "Default")
      (node (ref "IC1") (pin "18") (pinfunction "~{RESET}_18") (pintype "input"))
      (node (ref "R12") (pin "1") (pinfunction "1_1") (pintype "passive"))
    )
    (net (code "52") (name "Net-(IC2-~{RESET})") (class "Default")
      (node (ref "IC2") (pin "18") (pinfunction "~{RESET}_18") (pintype "input"))
      (node (ref "R18") (pin "1") (pinfunction "1_1") (pintype "passive"))
    )
    (net (code "53") (name "Net-(IC3-~{RESET})") (class "Default")
      (node (ref "IC3") (pin "18") (pinfunction "~{RESET}_18") (pintype "input"))
      (node (ref "R17") (pin "1") (pinfunction "1_1") (pintype "passive"))
    )
    (net (code "54") (name "Net-(J2-MIDI-Pad1)") (class "Default")
      (node (ref "J2-MIDI") (pin "1") (pinfunction "1_1") (pintype "passive"))
      (node (ref "R27") (pin "1") (pinfunction "1_1") (pintype "passive"))
    )
    (net (code "55") (name "Net-(J2-MIDI-Pad3)") (class "Default")
      (node (ref "J2-MIDI") (pin "3") (pinfunction "3_3") (pintype "passive"))
      (node (ref "R28") (pin "1") (pinfunction "1_1") (pintype "passive"))
    )
    (net (code "56") (name "Net-(LED1-C)") (class "Default")
      (node (ref "LED1") (pin "2") (pinfunction "C_2") (pintype "bidirectional"))
      (node (ref "R23") (pin "2") (pinfunction "2_2") (pintype "passive"))
    )
    (net (code "57") (name "Net-(LED2-C)") (class "Default")
      (node (ref "LED2") (pin "2") (pinfunction "C_2") (pintype "bidirectional"))
      (node (ref "R22") (pin "2") (pinfunction "2_2") (pintype "passive"))
    )
    (net (code "58") (name "Net-(LED3-C)") (class "Default")
      (node (ref "LED3") (pin "2") (pinfunction "C_2") (pintype "bidirectional"))
      (node (ref "R21") (pin "2") (pinfunction "2_2") (pintype "passive"))
    )
    (net (code "59") (name "Net-(LED4-C)") (class "Default")
      (node (ref "LED4") (pin "2") (pinfunction "C_2") (pintype "bidirectional"))
      (node (ref "R20") (pin "2") (pinfunction "2_2") (pintype "passive"))
    )
    (net (code "60") (name "Net-(LED5-C)") (class "Default")
      (node (ref "LED5") (pin "2") (pinfunction "C_2") (pintype "bidirectional"))
      (node (ref "R19") (pin "2") (pinfunction "2_2") (pintype "passive"))
    )
    (net (code "61") (name "Net-(LED8-PadA)") (class "Default")
      (node (ref "LED8") (pin "A") (pinfunction "A_A") (pintype "passive"))
      (node (ref "R15") (pin "1") (pinfunction "1_1") (pintype "passive"))
    )
    (net (code "62") (name "Net-(LED9-C)") (class "Default")
      (node (ref "LED9") (pin "2") (pinfunction "C_2") (pintype "bidirectional"))
      (node (ref "R16") (pin "2") (pinfunction "2_2") (pintype "passive"))
    )
    (net (code "63") (name "Net-(Q1-B)") (class "Default")
      (node (ref "Q1") (pin "1") (pinfunction "B_1") (pintype "passive"))
      (node (ref "R14") (pin "1") (pinfunction "1_1") (pintype "passive"))
    )
    (net (code "64") (name "Net-(Q1-C)") (class "Default")
      (node (ref "DISP1") (pin "1") (pinfunction "CA_1") (pintype "passive"))
      (node (ref "Q1") (pin "3") (pinfunction "C_3") (pintype "passive"))
    )
    (net (code "65") (name "Net-(Q2-B)") (class "Default")
      (node (ref "Q2") (pin "1") (pinfunction "B_1") (pintype "passive"))
      (node (ref "R13") (pin "1") (pinfunction "1_1") (pintype "passive"))
    )
    (net (code "66") (name "Net-(Q2-C)") (class "Default")
      (node (ref "DISP2") (pin "1") (pinfunction "CA_1") (pintype "passive"))
      (node (ref "Q2") (pin "3") (pinfunction "C_3") (pintype "passive"))
    )
    (net (code "67") (name "Net-(R68-Pad2)") (class "Default")
      (node (ref "R68") (pin "2") (pinfunction "2_2") (pintype "passive"))
      (node (ref "S4") (pin "A") (pinfunction "A_A") (pintype "passive"))
    )
    (net (code "68") (name "Net-(U1-AREF)") (class "Default")
      (node (ref "C5") (pin "1") (pinfunction "1_1") (pintype "passive"))
      (node (ref "U1") (pin "20") (pinfunction "AREF_20") (pintype "bidirectional"))
    )
    (net (code "69") (name "Net-(U1-AVCC)") (class "Default")
      (node (ref "C1") (pin "1") (pinfunction "1_1") (pintype "passive"))
      (node (ref "L1") (pin "2") (pinfunction "2_2") (pintype "passive"))
      (node (ref "U1") (pin "18") (pinfunction "AVCC_18") (pintype "bidirectional"))
    )
    (net (code "70") (name "Net-(U1-PB6(XTAL1{slash}TOSC1))") (class "Default")
      (node (ref "C2") (pin "2") (pinfunction "2_2") (pintype "passive"))
      (node (ref "U1") (pin "7") (pinfunction "PB6(XTAL1/TOSC1)_7") (pintype "bidirectional"))
      (node (ref "Y1") (pin "1") (pinfunction "1_1") (pintype "passive"))
    )
    (net (code "71") (name "Net-(U1-PB7(XTAL2{slash}TOSC2))") (class "Default")
      (node (ref "C3") (pin "2") (pinfunction "2_2") (pintype "passive"))
      (node (ref "U1") (pin "8") (pinfunction "PB7(XTAL2/TOSC2)_8") (pintype "bidirectional"))
      (node (ref "Y1") (pin "3") (pinfunction "2_3") (pintype "passive"))
    )
    (net (code "72") (name "OCT_DOWN") (class "Default")
      (node (ref "IC2") (pin "25") (pinfunction "GPA4_25") (pintype "bidirectional"))
      (node (ref "SW24") (pin "P2") (pinfunction "A2_P2") (pintype "passive"))
      (node (ref "SW24") (pin "P5") (pinfunction "B2_P5") (pintype "passive"))
    )
    (net (code "73") (name "OCT_LED1") (class "Default")
      (node (ref "IC2") (pin "2") (pinfunction "GPB1_2") (pintype "bidirectional"))
      (node (ref "LED5") (pin "1") (pinfunction "GRN_1") (pintype "bidirectional"))
    )
    (net (code "74") (name "OCT_LED2") (class "Default")
      (node (ref "IC2") (pin "3") (pinfunction "GPB2_3") (pintype "bidirectional"))
      (node (ref "LED5") (pin "3") (pinfunction "RED_3") (pintype "bidirectional"))
    )
    (net (code "75") (name "OCT_LED3") (class "Default")
      (node (ref "IC2") (pin "4") (pinfunction "GPB3_4") (pintype "bidirectional"))
      (node (ref "LED4") (pin "1") (pinfunction "GRN_1") (pintype "bidirectional"))
    )
    (net (code "76") (name "OCT_LED4") (class "Default")
      (node (ref "IC2") (pin "5") (pinfunction "GPB4_5") (pintype "bidirectional"))
      (node (ref "LED3") (pin "1") (pinfunction "GRN_1") (pintype "bidirectional"))
    )
    (net (code "77") (name "OCT_LED5") (class "Default")
      (node (ref "IC2") (pin "6") (pinfunction "GPB5_6") (pintype "bidirectional"))
      (node (ref "LED2") (pin "1") (pinfunction "GRN_1") (pintype "bidirectional"))
    )
    (net (code "78") (name "OCT_LED6") (class "Default")
      (node (ref "IC2") (pin "7") (pinfunction "GPB6_7") (pintype "bidirectional"))
      (node (ref "LED1") (pin "1") (pinfunction "GRN_1") (pintype "bidirectional"))
    )
    (net (code "79") (name "OCT_LED7") (class "Default")
      (node (ref "IC2") (pin "8") (pinfunction "GPB7_8") (pintype "bidirectional"))
      (node (ref "LED1") (pin "3") (pinfunction "RED_3") (pintype "bidirectional"))
    )
    (net (code "80") (name "OCT_UP") (class "Default")
      (node (ref "IC2") (pin "24") (pinfunction "GPA3_24") (pintype "bidirectional"))
      (node (ref "SW25") (pin "P2") (pinfunction "A2_P2") (pintype "passive"))
      (node (ref "SW25") (pin "P5") (pinfunction "B2_P5") (pintype "passive"))
    )
    (net (code "81") (name "OSC") (class "Default")
      (node (ref "S6") (pin "O") (pinfunction "O_O") (pintype "passive"))
      (node (ref "U1") (pin "32") (pinfunction "PD2(INT0)_32") (pintype "bidirectional"))
    )
    (net (code "82") (name "POT_MUX") (class "Default")
      (node (ref "IC6") (pin "3") (pinfunction "X_3") (pintype "bidirectional"))
      (node (ref "U1") (pin "23") (pinfunction "PC0(ADC0)_23") (pintype "bidirectional"))
    )
    (net (code "83") (name "POT_VAL_COM") (class "Default")
      (node (ref "R13") (pin "2") (pinfunction "2_2") (pintype "passive"))
      (node (ref "U1") (pin "12") (pinfunction "PB0(ICP)_12") (pintype "bidirectional"))
    )
    (net (code "84") (name "RESET") (class "Default")
      (node (ref "J3") (pin "5") (pinfunction "5_5") (pintype "passive"))
      (node (ref "R9") (pin "1") (pinfunction "1_1") (pintype "passive"))
      (node (ref "U1") (pin "29") (pinfunction "PC6(/RESET)_29") (pintype "bidirectional"))
    )
    (net (code "85") (name "REST") (class "Default")
      (node (ref "SW2") (pin "A1") (pinfunction "S_A1") (pintype "passive"))
      (node (ref "SW2") (pin "A2") (pinfunction "S1_A2") (pintype "passive"))
      (node (ref "U1") (pin "10") (pinfunction "PD6(AIN0)_10") (pintype "bidirectional"))
    )
    (net (code "86") (name "SCK") (class "Default")
      (node (ref "J3") (pin "3") (pinfunction "3_3") (pintype "passive"))
      (node (ref "S7") (pin "3") (pinfunction "3_3") (pintype "passive"))
      (node (ref "S7") (pin "4") (pinfunction "4_4") (pintype "passive"))
      (node (ref "U1") (pin "17") (pinfunction "PB5(SCK)_17") (pintype "bidirectional"))
    )
    (net (code "87") (name "SEG1_A") (class "Default")
      (node (ref "IC3") (pin "21") (pinfunction "GPA0_21") (pintype "bidirectional"))
      (node (ref "R57") (pin "2") (pinfunction "2_2") (pintype "passive"))
    )
    (net (code "88") (name "SEG1_B") (class "Default")
      (node (ref "IC3") (pin "22") (pinfunction "GPA1_22") (pintype "bidirectional"))
      (node (ref "R58") (pin "2") (pinfunction "2_2") (pintype "passive"))
    )
    (net (code "89") (name "SEG1_C") (class "Default")
      (node (ref "IC3") (pin "23") (pinfunction "GPA2_23") (pintype "bidirectional"))
      (node (ref "R59") (pin "2") (pinfunction "2_2") (pintype "passive"))
    )
    (net (code "90") (name "SEG1_D") (class "Default")
      (node (ref "IC3") (pin "24") (pinfunction "GPA3_24") (pintype "bidirectional"))
      (node (ref "R60") (pin "2") (pinfunction "2_2") (pintype "passive"))
    )
    (net (code "91") (name "SEG1_E") (class "Default")
      (node (ref "IC3") (pin "25") (pinfunction "GPA4_25") (pintype "bidirectional"))
      (node (ref "R61") (pin "2") (pinfunction "2_2") (pintype "passive"))
    )
    (net (code "92") (name "SEG1_F") (class "Default")
      (node (ref "IC3") (pin "26") (pinfunction "GPA5_26") (pintype "bidirectional"))
      (node (ref "R62") (pin "2") (pinfunction "2_2") (pintype "passive"))
    )
    (net (code "93") (name "SEG1_G") (class "Default")
      (node (ref "IC3") (pin "27") (pinfunction "GPA6_27") (pintype "bidirectional"))
      (node (ref "R63") (pin "2") (pinfunction "2_2") (pintype "passive"))
    )
    (net (code "94") (name "SEG2_A") (class "Default")
      (node (ref "IC3") (pin "1") (pinfunction "GPB0_1") (pintype "bidirectional"))
      (node (ref "R47") (pin "2") (pinfunction "2_2") (pintype "passive"))
    )
    (net (code "95") (name "SEG2_B") (class "Default")
      (node (ref "IC3") (pin "2") (pinfunction "GPB1_2") (pintype "bidirectional"))
      (node (ref "R48") (pin "2") (pinfunction "2_2") (pintype "passive"))
    )
    (net (code "96") (name "SEG2_C") (class "Default")
      (node (ref "IC3") (pin "3") (pinfunction "GPB2_3") (pintype "bidirectional"))
      (node (ref "R51") (pin "2") (pinfunction "2_2") (pintype "passive"))
    )
    (net (code "97") (name "SEG2_D") (class "Default")
      (node (ref "IC3") (pin "4") (pinfunction "GPB3_4") (pintype "bidirectional"))
      (node (ref "R52") (pin "2") (pinfunction "2_2") (pintype "passive"))
    )
    (net (code "98") (name "SEG2_DP") (class "Default")
      (node (ref "IC3") (pin "8") (pinfunction "GPB7_8") (pintype "bidirectional"))
      (node (ref "R56") (pin "1") (pinfunction "1_1") (pintype "passive"))
    )
    (net (code "99") (name "SEG2_E") (class "Default")
      (node (ref "IC3") (pin "5") (pinfunction "GPB4_5") (pintype "bidirectional"))
      (node (ref "R53") (pin "2") (pinfunction "2_2") (pintype "passive"))
    )
    (net (code "100") (name "SEG2_F") (class "Default")
      (node (ref "IC3") (pin "6") (pinfunction "GPB5_6") (pintype "bidirectional"))
      (node (ref "R54") (pin "2") (pinfunction "2_2") (pintype "passive"))
    )
    (net (code "101") (name "SEG2_G") (class "Default")
      (node (ref "IC3") (pin "7") (pinfunction "GPB6_7") (pintype "bidirectional"))
      (node (ref "R55") (pin "2") (pinfunction "2_2") (pintype "passive"))
    )
    (net (code "102") (name "SHIFT_BUTT") (class "Default")
      (node (ref "IC2") (pin "26") (pinfunction "GPA5_26") (pintype "bidirectional"))
      (node (ref "S4") (pin "3") (pinfunction "1_3") (pintype "passive"))
      (node (ref "S4") (pin "4") (pinfunction "1_4") (pintype "passive"))
    )
    (net (code "103") (name "SHIFT_LED") (class "Default")
      (node (ref "IC2") (pin "27") (pinfunction "GPA6_27") (pintype "bidirectional"))
      (node (ref "R68") (pin "1") (pinfunction "1_1") (pintype "passive"))
    )
    (net (code "104") (name "SLIDE") (class "Default")
      (node (ref "SW3") (pin "A1") (pinfunction "S_A1") (pintype "passive"))
      (node (ref "SW3") (pin "A2") (pinfunction "S1_A2") (pintype "passive"))
      (node (ref "U1") (pin "24") (pinfunction "PC1(ADC1)_24") (pintype "bidirectional"))
    )
    (net (code "105") (name "STEP_4") (class "Default")
      (node (ref "S3") (pin "3") (pinfunction "3_3") (pintype "passive"))
      (node (ref "S3") (pin "4") (pinfunction "4_4") (pintype "passive"))
      (node (ref "U1") (pin "9") (pinfunction "PD5(T1)_9") (pintype "bidirectional"))
    )
    (net (code "106") (name "STEP_8") (class "Default")
      (node (ref "S2") (pin "3") (pinfunction "3_3") (pintype "passive"))
      (node (ref "S2") (pin "4") (pinfunction "4_4") (pintype "passive"))
      (node (ref "U1") (pin "2") (pinfunction "PD4(XCK/T0)_2") (pintype "bidirectional"))
    )
    (net (code "107") (name "TIE") (class "Default")
      (node (ref "SW1") (pin "A1") (pinfunction "S_A1") (pintype "passive"))
      (node (ref "SW1") (pin "A2") (pinfunction "S1_A2") (pintype "passive"))
      (node (ref "U1") (pin "25") (pinfunction "PC2(ADC2)_25") (pintype "bidirectional"))
    )
    (net (code "108") (name "VCC") (class "Default")
      (node (ref "C6") (pin "+") (pinfunction "+_+") (pintype "passive"))
      (node (ref "D2") (pin "C") (pinfunction "C_C") (pintype "passive"))
      (node (ref "IC5") (pin "3") (pinfunction "VIN_3") (pintype "input"))
    )
    (net (code "109") (name "VEL_SLIDE") (class "Default")
      (node (ref "U1") (pin "26") (pinfunction "PC3(ADC3)_26") (pintype "bidirectional"))
      (node (ref "VR1") (pin "TOP") (pinfunction "E_TOP") (pintype "passive"))
    )
    (net (code "110") (name "X0") (class "Default")
      (node (ref "IC6") (pin "13") (pinfunction "X0_13") (pintype "bidirectional"))
      (node (ref "R1") (pin "P$2") (pinfunction "S_P$2") (pintype "passive"))
    )
    (net (code "111") (name "X1") (class "Default")
      (node (ref "IC6") (pin "14") (pinfunction "X1_14") (pintype "bidirectional"))
      (node (ref "R2") (pin "P$2") (pinfunction "S_P$2") (pintype "passive"))
    )
    (net (code "112") (name "X2") (class "Default")
      (node (ref "IC6") (pin "15") (pinfunction "X2_15") (pintype "bidirectional"))
      (node (ref "R3") (pin "P$2") (pinfunction "S_P$2") (pintype "passive"))
    )
    (net (code "113") (name "X3") (class "Default")
      (node (ref "IC6") (pin "12") (pinfunction "X3_12") (pintype "bidirectional"))
      (node (ref "R4") (pin "P$2") (pinfunction "S_P$2") (pintype "passive"))
    )
    (net (code "114") (name "X4") (class "Default")
      (node (ref "IC6") (pin "1") (pinfunction "X4_1") (pintype "bidirectional"))
      (node (ref "R5") (pin "P$2") (pinfunction "S_P$2") (pintype "passive"))
    )
    (net (code "115") (name "X5") (class "Default")
      (node (ref "IC6") (pin "5") (pinfunction "X5_5") (pintype "bidirectional"))
      (node (ref "R6") (pin "P$2") (pinfunction "S_P$2") (pintype "passive"))
    )
    (net (code "116") (name "X6") (class "Default")
      (node (ref "IC6") (pin "2") (pinfunction "X6_2") (pintype "bidirectional"))
      (node (ref "R7") (pin "P$2") (pinfunction "S_P$2") (pintype "passive"))
    )
    (net (code "117") (name "X7") (class "Default")
      (node (ref "IC6") (pin "4") (pinfunction "X7_4") (pintype "bidirectional"))
      (node (ref "R8") (pin "P$2") (pinfunction "S_P$2") (pintype "passive"))
    )
    (net (code "118") (name "XTRA") (class "Default")
      (node (ref "IC2") (pin "1") (pinfunction "GPB0_1") (pintype "bidirectional"))
      (node (ref "S5") (pin "3") (pinfunction "3_3") (pintype "passive"))
      (node (ref "S5") (pin "4") (pinfunction "4_4") (pintype "passive"))
    )
    (net (code "119") (name "unconnected-(DISP1-CA-Pad6)") (class "Default")
      (node (ref "DISP1") (pin "6") (pinfunction "CA_6") (pintype "passive"))
    )
    (net (code "120") (name "unconnected-(DISP1-DP-Pad7)") (class "Default")
      (node (ref "DISP1") (pin "7") (pinfunction "DP_7") (pintype "passive"))
    )
    (net (code "121") (name "unconnected-(DISP2-CA-Pad6)") (class "Default")
      (node (ref "DISP2") (pin "6") (pinfunction "CA_6") (pintype "passive"))
    )
    (net (code "122") (name "unconnected-(IC1-INTA-Pad20)") (class "Default")
      (node (ref "IC1") (pin "20") (pinfunction "INTA_20") (pintype "output"))
    )
    (net (code "123") (name "unconnected-(IC1-INTB-Pad19)") (class "Default")
      (node (ref "IC1") (pin "19") (pinfunction "INTB_19") (pintype "output"))
    )
    (net (code "124") (name "unconnected-(IC2-INTA-Pad20)") (class "Default")
      (node (ref "IC2") (pin "20") (pinfunction "INTA_20") (pintype "output"))
    )
    (net (code "125") (name "unconnected-(IC2-INTB-Pad19)") (class "Default")
      (node (ref "IC2") (pin "19") (pinfunction "INTB_19") (pintype "output"))
    )
    (net (code "126") (name "unconnected-(IC3-INTA-Pad20)") (class "Default")
      (node (ref "IC3") (pin "20") (pinfunction "INTA_20") (pintype "output"))
    )
    (net (code "127") (name "unconnected-(IC3-INTB-Pad19)") (class "Default")
      (node (ref "IC3") (pin "19") (pinfunction "INTB_19") (pintype "output"))
    )
    (net (code "128") (name "unconnected-(LED2-RED-Pad3)") (class "Default")
      (node (ref "LED2") (pin "3") (pinfunction "RED_3") (pintype "bidirectional"))
    )
    (net (code "129") (name "unconnected-(LED3-RED-Pad3)") (class "Default")
      (node (ref "LED3") (pin "3") (pinfunction "RED_3") (pintype "bidirectional"))
    )
    (net (code "130") (name "unconnected-(LED4-RED-Pad3)") (class "Default")
      (node (ref "LED4") (pin "3") (pinfunction "RED_3") (pintype "bidirectional"))
    )
    (net (code "131") (name "unconnected-(SW4-A1-PadP1)") (class "Default")
      (node (ref "SW4") (pin "P1") (pinfunction "A1_P1") (pintype "passive"))
    )
    (net (code "132") (name "unconnected-(SW4-B1-PadP4)") (class "Default")
      (node (ref "SW4") (pin "P4") (pinfunction "B1_P4") (pintype "passive"))
    )
    (net (code "133") (name "unconnected-(SW5-A1-PadP1)") (class "Default")
      (node (ref "SW5") (pin "P1") (pinfunction "A1_P1") (pintype "passive"))
    )
    (net (code "134") (name "unconnected-(SW5-B1-PadP4)") (class "Default")
      (node (ref "SW5") (pin "P4") (pinfunction "B1_P4") (pintype "passive"))
    )
    (net (code "135") (name "unconnected-(SW6-A1-PadP1)") (class "Default")
      (node (ref "SW6") (pin "P1") (pinfunction "A1_P1") (pintype "passive"))
    )
    (net (code "136") (name "unconnected-(SW6-B1-PadP4)") (class "Default")
      (node (ref "SW6") (pin "P4") (pinfunction "B1_P4") (pintype "passive"))
    )
    (net (code "137") (name "unconnected-(SW7-A1-PadP1)") (class "Default")
      (node (ref "SW7") (pin "P1") (pinfunction "A1_P1") (pintype "passive"))
    )
    (net (code "138") (name "unconnected-(SW7-B1-PadP4)") (class "Default")
      (node (ref "SW7") (pin "P4") (pinfunction "B1_P4") (pintype "passive"))
    )
    (net (code "139") (name "unconnected-(SW8-A1-PadP1)") (class "Default")
      (node (ref "SW8") (pin "P1") (pinfunction "A1_P1") (pintype "passive"))
    )
    (net (code "140") (name "unconnected-(SW8-B1-PadP4)") (class "Default")
      (node (ref "SW8") (pin "P4") (pinfunction "B1_P4") (pintype "passive"))
    )
    (net (code "141") (name "unconnected-(SW9-A1-PadP1)") (class "Default")
      (node (ref "SW9") (pin "P1") (pinfunction "A1_P1") (pintype "passive"))
    )
    (net (code "142") (name "unconnected-(SW9-B1-PadP4)") (class "Default")
      (node (ref "SW9") (pin "P4") (pinfunction "B1_P4") (pintype "passive"))
    )
    (net (code "143") (name "unconnected-(SW10-A1-PadP1)") (class "Default")
      (node (ref "SW10") (pin "P1") (pinfunction "A1_P1") (pintype "passive"))
    )
    (net (code "144") (name "unconnected-(SW10-B1-PadP4)") (class "Default")
      (node (ref "SW10") (pin "P4") (pinfunction "B1_P4") (pintype "passive"))
    )
    (net (code "145") (name "unconnected-(SW11-A1-PadP1)") (class "Default")
      (node (ref "SW11") (pin "P1") (pinfunction "A1_P1") (pintype "passive"))
    )
    (net (code "146") (name "unconnected-(SW11-B1-PadP4)") (class "Default")
      (node (ref "SW11") (pin "P4") (pinfunction "B1_P4") (pintype "passive"))
    )
    (net (code "147") (name "unconnected-(SW12-A1-PadP1)") (class "Default")
      (node (ref "SW12") (pin "P1") (pinfunction "A1_P1") (pintype "passive"))
    )
    (net (code "148") (name "unconnected-(SW12-B1-PadP4)") (class "Default")
      (node (ref "SW12") (pin "P4") (pinfunction "B1_P4") (pintype "passive"))
    )
    (net (code "149") (name "unconnected-(SW13-A1-PadP1)") (class "Default")
      (node (ref "SW13") (pin "P1") (pinfunction "A1_P1") (pintype "passive"))
    )
    (net (code "150") (name "unconnected-(SW13-B1-PadP4)") (class "Default")
      (node (ref "SW13") (pin "P4") (pinfunction "B1_P4") (pintype "passive"))
    )
    (net (code "151") (name "unconnected-(SW14-A1-PadP1)") (class "Default")
      (node (ref "SW14") (pin "P1") (pinfunction "A1_P1") (pintype "passive"))
    )
    (net (code "152") (name "unconnected-(SW14-B1-PadP4)") (class "Default")
      (node (ref "SW14") (pin "P4") (pinfunction "B1_P4") (pintype "passive"))
    )
    (net (code "153") (name "unconnected-(SW15-A1-PadP1)") (class "Default")
      (node (ref "SW15") (pin "P1") (pinfunction "A1_P1") (pintype "passive"))
    )
    (net (code "154") (name "unconnected-(SW15-B1-PadP4)") (class "Default")
      (node (ref "SW15") (pin "P4") (pinfunction "B1_P4") (pintype "passive"))
    )
    (net (code "155") (name "unconnected-(SW16-A1-PadP1)") (class "Default")
      (node (ref "SW16") (pin "P1") (pinfunction "A1_P1") (pintype "passive"))
    )
    (net (code "156") (name "unconnected-(SW16-B1-PadP4)") (class "Default")
      (node (ref "SW16") (pin "P4") (pinfunction "B1_P4") (pintype "passive"))
    )
    (net (code "157") (name "unconnected-(SW17-A1-PadP1)") (class "Default")
      (node (ref "SW17") (pin "P1") (pinfunction "A1_P1") (pintype "passive"))
    )
    (net (code "158") (name "unconnected-(SW17-B1-PadP4)") (class "Default")
      (node (ref "SW17") (pin "P4") (pinfunction "B1_P4") (pintype "passive"))
    )
    (net (code "159") (name "unconnected-(SW18-A1-PadP1)") (class "Default")
      (node (ref "SW18") (pin "P1") (pinfunction "A1_P1") (pintype "passive"))
    )
    (net (code "160") (name "unconnected-(SW18-B1-PadP4)") (class "Default")
      (node (ref "SW18") (pin "P4") (pinfunction "B1_P4") (pintype "passive"))
    )
    (net (code "161") (name "unconnected-(SW19-A1-PadP1)") (class "Default")
      (node (ref "SW19") (pin "P1") (pinfunction "A1_P1") (pintype "passive"))
    )
    (net (code "162") (name "unconnected-(SW19-B1-PadP4)") (class "Default")
      (node (ref "SW19") (pin "P4") (pinfunction "B1_P4") (pintype "passive"))
    )
    (net (code "163") (name "unconnected-(SW20-A1-PadP1)") (class "Default")
      (node (ref "SW20") (pin "P1") (pinfunction "A1_P1") (pintype "passive"))
    )
    (net (code "164") (name "unconnected-(SW20-B1-PadP4)") (class "Default")
      (node (ref "SW20") (pin "P4") (pinfunction "B1_P4") (pintype "passive"))
    )
    (net (code "165") (name "unconnected-(SW21-A1-PadP1)") (class "Default")
      (node (ref "SW21") (pin "P1") (pinfunction "A1_P1") (pintype "passive"))
    )
    (net (code "166") (name "unconnected-(SW21-B1-PadP4)") (class "Default")
      (node (ref "SW21") (pin "P4") (pinfunction "B1_P4") (pintype "passive"))
    )
    (net (code "167") (name "unconnected-(SW24-A1-PadP1)") (class "Default")
      (node (ref "SW24") (pin "P1") (pinfunction "A1_P1") (pintype "passive"))
    )
    (net (code "168") (name "unconnected-(SW24-B1-PadP4)") (class "Default")
      (node (ref "SW24") (pin "P4") (pinfunction "B1_P4") (pintype "passive"))
    )
    (net (code "169") (name "unconnected-(SW25-A1-PadP1)") (class "Default")
      (node (ref "SW25") (pin "P1") (pinfunction "A1_P1") (pintype "passive"))
    )
    (net (code "170") (name "unconnected-(SW25-B1-PadP4)") (class "Default")
      (node (ref "SW25") (pin "P4") (pinfunction "B1_P4") (pintype "passive"))
    )
    (net (code "171") (name "unconnected-(U1-PD0(RXD)-Pad30)") (class "Default")
      (node (ref "U1") (pin "30") (pinfunction "PD0(RXD)_30") (pintype "bidirectional"))
    )
  )
)
